# BG95_Power.net
KiCad netlist of a schematic drawn in Altium Designer
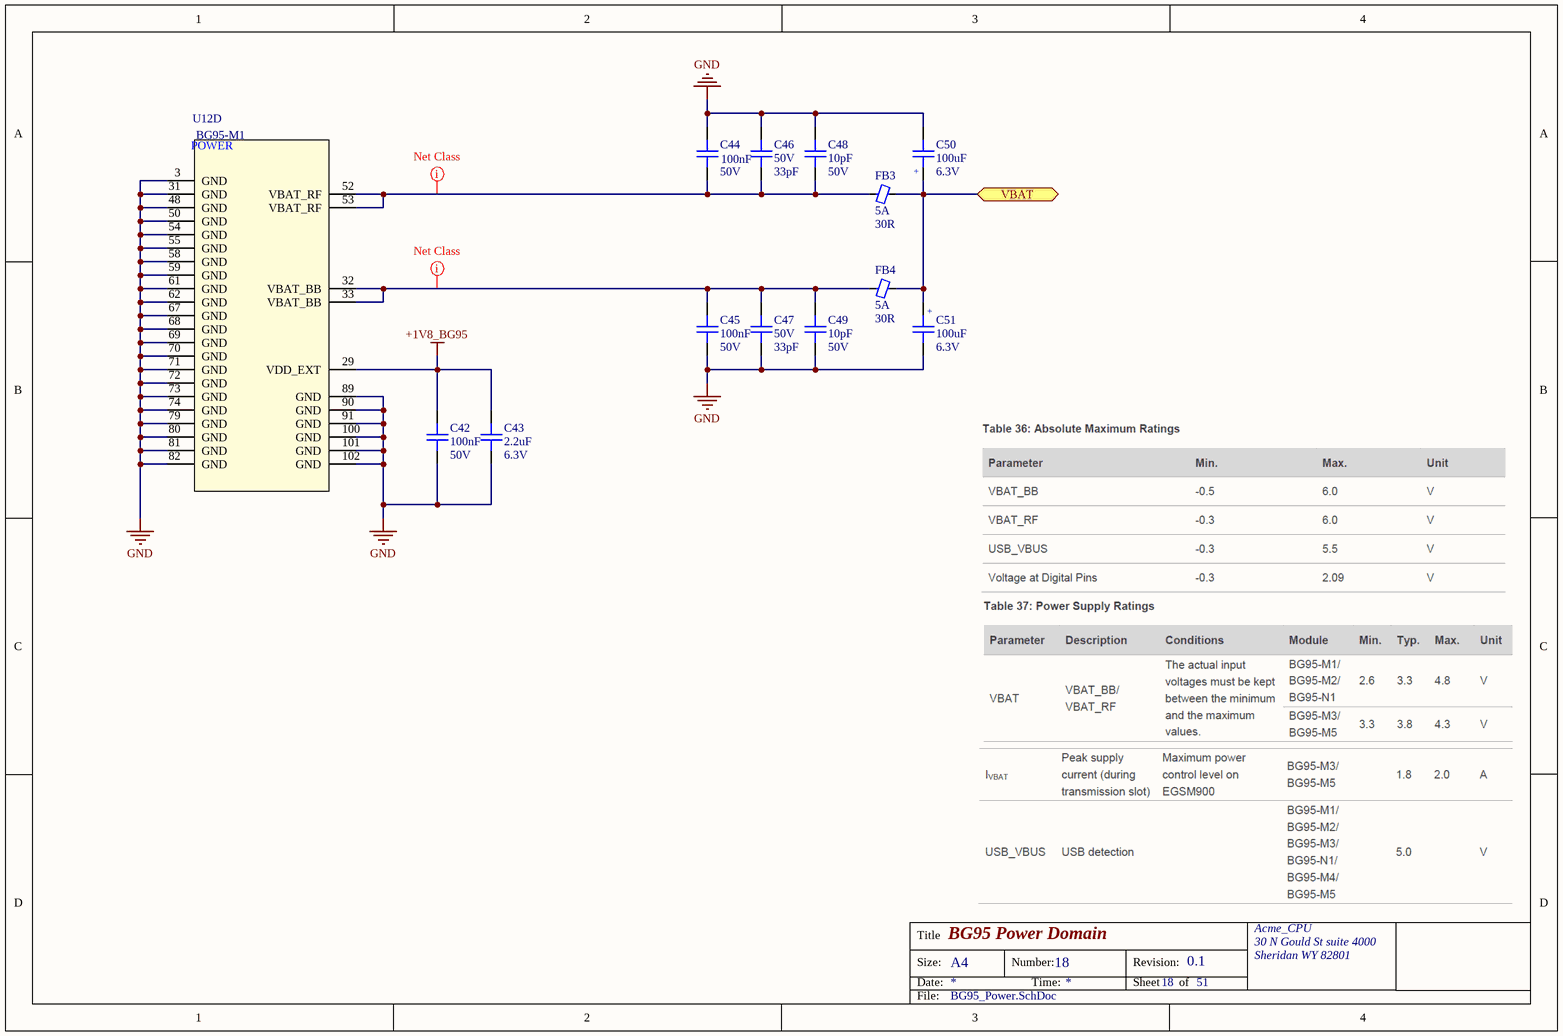
[diagram p0: BG95_Power.SchDoc]

(export (version "E")
  (design (tool "Eeschema 10.0.6"))
  (components
    (comp (ref "C42")
      (value "CAP CER 0.1UF 50V X7R 0402")
      (footprint "C0402")
      (description "0.1µF ±10% 50V Ceramic Capacitor X7R 0402 (1005 Metric)")
      (fields
        (field (name "MANUFACTURER") "TDK")
        (field (name "MANUFACTURER PART NUMBER") "CGA2B3X7R1H104K050BB")
        (field (name "CAPACITANCE") "100nF")
        (field (name "VOLTAGE") "50V")
      )
      (libsource (lib "capacitors_smd") (part "CAP CER 0.1UF 50V X7R 0402"))
    )
    (comp (ref "C43")
      (value "CAP CER 2.2UF 6.3V X5R 0402")
      (footprint "C0402")
      (description "2.2µF ±20% 6.3V Ceramic Capacitor X5R 0402 (1005 Metric)")
      (fields
        (field (name "MANUFACTURER") "Murata")
        (field (name "MANUFACTURER PART NUMBER") "GRM155R60J225ME15D")
        (field (name "CAPACITANCE") "2.2uF")
        (field (name "VOLTAGE") "6.3V")
      )
      (libsource (lib "capacitors_smd") (part "CAP CER 2.2UF 6.3V X5R 0402"))
    )
    (comp (ref "C44")
      (value "CAP CER 0.1UF 50V X7R 0402")
      (footprint "C0402")
      (description "0.1µF ±10% 50V Ceramic Capacitor X7R 0402 (1005 Metric)")
      (fields
        (field (name "MANUFACTURER") "TDK")
        (field (name "MANUFACTURER PART NUMBER") "CGA2B3X7R1H104K050BB")
        (field (name "CAPACITANCE") "100nF")
        (field (name "VOLTAGE") "50V")
      )
      (libsource (lib "capacitors_smd") (part "CAP CER 0.1UF 50V X7R 0402"))
    )
    (comp (ref "C45")
      (value "CAP CER 0.1UF 50V X7R 0402")
      (footprint "C0402")
      (description "0.1µF ±10% 50V Ceramic Capacitor X7R 0402 (1005 Metric)")
      (fields
        (field (name "MANUFACTURER") "TDK")
        (field (name "MANUFACTURER PART NUMBER") "CGA2B3X7R1H104K050BB")
        (field (name "CAPACITANCE") "100nF")
        (field (name "VOLTAGE") "50V")
      )
      (libsource (lib "capacitors_smd") (part "CAP CER 0.1UF 50V X7R 0402"))
    )
    (comp (ref "C46")
      (value "CAP CER 33PF 50V C0G/NPO 0402")
      (footprint "C0402")
      (description "33pF ±5% 50V Ceramic Capacitor C0G, NP0 0402 (1005 Metric)")
      (fields
        (field (name "MANUFACTURER") "Yageo")
        (field (name "MANUFACTURER PART NUMBER") "CC0402JRNPO9BN330")
        (field (name "VOLTAGE RATING") "50V")
        (field (name "CAPACITANCE") "33pF")
      )
      (libsource (lib "capacitors_smd") (part "CAP CER 33PF 50V C0G/NPO 0402"))
    )
    (comp (ref "C47")
      (value "CAP CER 33PF 50V C0G/NPO 0402")
      (footprint "C0402")
      (description "33pF ±5% 50V Ceramic Capacitor C0G, NP0 0402 (1005 Metric)")
      (fields
        (field (name "MANUFACTURER") "Yageo")
        (field (name "MANUFACTURER PART NUMBER") "CC0402JRNPO9BN330")
        (field (name "VOLTAGE RATING") "50V")
        (field (name "CAPACITANCE") "33pF")
      )
      (libsource (lib "capacitors_smd") (part "CAP CER 33PF 50V C0G/NPO 0402"))
    )
    (comp (ref "C48")
      (value "CAP CER 10PF 50V C0G/NP0 0402")
      (footprint "C0402")
      (description "10pF ±10% 50V Ceramic Capacitor C0G, NP0 0402 (1005 Metric)")
      (fields
        (field (name "MANUFACTURER") "KEMET")
        (field (name "MANUFACTURER PART NUMBER") "C0402C100K5GACTU")
        (field (name "CAPACITANCE") "10pF")
        (field (name "VOLTAGE RATING") "50V")
      )
      (libsource (lib "capacitors_smd") (part "CAP CER 10PF 50V C0G/NP0 0402"))
    )
    (comp (ref "C49")
      (value "CAP CER 10PF 50V C0G/NP0 0402")
      (footprint "C0402")
      (description "10pF ±10% 50V Ceramic Capacitor C0G, NP0 0402 (1005 Metric)")
      (fields
        (field (name "MANUFACTURER") "KEMET")
        (field (name "MANUFACTURER PART NUMBER") "C0402C100K5GACTU")
        (field (name "CAPACITANCE") "10pF")
        (field (name "VOLTAGE RATING") "50V")
      )
      (libsource (lib "capacitors_smd") (part "CAP CER 10PF 50V C0G/NP0 0402"))
    )
    (comp (ref "C50")
      (value "CAP ALUM 100 UF 20% 6.3 V SMD")
      (footprint "WCAP-ASLI_5x5.5")
      (description "100µF 6.3V Aluminum Electrolytic Capacitors Radial, Can - SMD  2000 Hrs @ 105°C")
      (fields
        (field (name "MANUFACTURER") "Wurth Elektronik")
        (field (name "MANUFACTURER PART NUMBER") "865080142007")
        (field (name "CAPACITANCE") "100uF")
        (field (name "VOLTAGE RATING") "6.3V")
      )
      (libsource (lib "capacitors_alum_electr_poly") (part "CAP ALUM 100 UF 20% 6.3 V SMD"))
    )
    (comp (ref "C51")
      (value "CAP ALUM 100 UF 20% 6.3 V SMD")
      (footprint "WCAP-ASLI_5x5.5")
      (description "100µF 6.3V Aluminum Electrolytic Capacitors Radial, Can - SMD  2000 Hrs @ 105°C")
      (fields
        (field (name "MANUFACTURER") "Wurth Elektronik")
        (field (name "MANUFACTURER PART NUMBER") "865080142007")
        (field (name "CAPACITANCE") "100uF")
        (field (name "VOLTAGE RATING") "6.3V")
      )
      (libsource (lib "capacitors_alum_electr_poly") (part "CAP ALUM 100 UF 20% 6.3 V SMD"))
    )
    (comp (ref "FB3")
      (value "MPZ1608S300ATAH0")
      (footprint "L0603")
      (description "30 Ohms @ 100MHz 1 Power Line Ferrite Bead 0603 (1608 Metric) 5A 10mOhm")
      (fields
        (field (name "MANUFACTURER") "TDK")
        (field (name "TOLERANCE") "25%")
        (field (name "CURRENT RATING") "5A")
        (field (name "IMPEDANCE") "30R")
      )
      (libsource (lib "ferrite_beads") (part "FERRITE BEAD 30 OHM 0603 1LN"))
    )
    (comp (ref "FB4")
      (value "MPZ1608S300ATAH0")
      (footprint "L0603")
      (description "30 Ohms @ 100MHz 1 Power Line Ferrite Bead 0603 (1608 Metric) 5A 10mOhm")
      (fields
        (field (name "MANUFACTURER") "TDK")
        (field (name "TOLERANCE") "25%")
        (field (name "CURRENT RATING") "5A")
        (field (name "IMPEDANCE") "30R")
      )
      (libsource (lib "ferrite_beads") (part "FERRITE BEAD 30 OHM 0603 1LN"))
    )
    (comp (ref "U12")
      (value "BG95-M1")
      (footprint "BG95")
      (description "LTE Cat M1, LTE Cat NB2 and EGPRS Transceiver Module Antenna Not Included Surface Mount")
      (fields (field (name "MANUFACTURER") "QUECTEL"))
      (libsource (lib "BLDC_Motor_Driver") (part "MOD BG95 RX TXRX CELLULAR LTE/NAV SMD"))
    )
  )
  (nets
    (net (code "1") (name "+1V8_BG95") (class "Default")
      (node (ref "C42") (pin "2") (pinfunction "2_2") (pintype "passive"))
      (node (ref "C43") (pin "2") (pinfunction "2_2") (pintype "passive"))
      (node (ref "U12") (pin "29") (pinfunction "VDD_EXT_29") (pintype "power_in"))
    )
    (net (code "2") (name "/VBAT") (class "Default")
      (node (ref "C50") (pin "1") (pinfunction "1_1") (pintype "passive"))
      (node (ref "C51") (pin "1") (pinfunction "1_1") (pintype "passive"))
      (node (ref "FB3") (pin "2") (pinfunction "2_2") (pintype "passive"))
      (node (ref "FB4") (pin "2") (pinfunction "2_2") (pintype "passive"))
    )
    (net (code "3") (name "GND") (class "Default")
      (node (ref "C42") (pin "1") (pinfunction "1_1") (pintype "passive"))
      (node (ref "C43") (pin "1") (pinfunction "1_1") (pintype "passive"))
      (node (ref "C44") (pin "2") (pinfunction "2_2") (pintype "passive"))
      (node (ref "C45") (pin "1") (pinfunction "1_1") (pintype "passive"))
      (node (ref "C46") (pin "2") (pinfunction "2_2") (pintype "passive"))
      (node (ref "C47") (pin "1") (pinfunction "1_1") (pintype "passive"))
      (node (ref "C48") (pin "2") (pinfunction "2_2") (pintype "passive"))
      (node (ref "C49") (pin "1") (pinfunction "1_1") (pintype "passive"))
      (node (ref "C50") (pin "2") (pinfunction "2_2") (pintype "passive"))
      (node (ref "C51") (pin "2") (pinfunction "2_2") (pintype "passive"))
      (node (ref "U12") (pin "100") (pinfunction "GND_100") (pintype "power_in"))
      (node (ref "U12") (pin "101") (pinfunction "GND_101") (pintype "power_in"))
      (node (ref "U12") (pin "102") (pinfunction "GND_102") (pintype "power_in"))
      (node (ref "U12") (pin "3") (pinfunction "GND_3") (pintype "power_in"))
      (node (ref "U12") (pin "31") (pinfunction "GND_31") (pintype "power_in"))
      (node (ref "U12") (pin "48") (pinfunction "GND_48") (pintype "power_in"))
      (node (ref "U12") (pin "50") (pinfunction "GND_50") (pintype "power_in"))
      (node (ref "U12") (pin "54") (pinfunction "GND_54") (pintype "power_in"))
      (node (ref "U12") (pin "55") (pinfunction "GND_55") (pintype "power_in"))
      (node (ref "U12") (pin "58") (pinfunction "GND_58") (pintype "power_in"))
      (node (ref "U12") (pin "59") (pinfunction "GND_59") (pintype "power_in"))
      (node (ref "U12") (pin "61") (pinfunction "GND_61") (pintype "power_in"))
      (node (ref "U12") (pin "62") (pinfunction "GND_62") (pintype "power_in"))
      (node (ref "U12") (pin "67") (pinfunction "GND_67") (pintype "power_in"))
      (node (ref "U12") (pin "68") (pinfunction "GND_68") (pintype "power_in"))
      (node (ref "U12") (pin "69") (pinfunction "GND_69") (pintype "power_in"))
      (node (ref "U12") (pin "70") (pinfunction "GND_70") (pintype "power_in"))
      (node (ref "U12") (pin "71") (pinfunction "GND_71") (pintype "power_in"))
      (node (ref "U12") (pin "72") (pinfunction "GND_72") (pintype "power_in"))
      (node (ref "U12") (pin "73") (pinfunction "GND_73") (pintype "power_in"))
      (node (ref "U12") (pin "74") (pinfunction "GND_74") (pintype "power_in"))
      (node (ref "U12") (pin "79") (pinfunction "GND_79") (pintype "power_in"))
      (node (ref "U12") (pin "80") (pinfunction "GND_80") (pintype "power_in"))
      (node (ref "U12") (pin "81") (pinfunction "GND_81") (pintype "power_in"))
      (node (ref "U12") (pin "82") (pinfunction "GND_82") (pintype "power_in"))
      (node (ref "U12") (pin "89") (pinfunction "GND_89") (pintype "power_in"))
      (node (ref "U12") (pin "90") (pinfunction "GND_90") (pintype "power_in"))
      (node (ref "U12") (pin "91") (pinfunction "GND_91") (pintype "power_in"))
    )
    (net (code "4") (name "Net-(C44-Pad1)") (class "Default")
      (node (ref "C44") (pin "1") (pinfunction "1_1") (pintype "passive"))
      (node (ref "C46") (pin "1") (pinfunction "1_1") (pintype "passive"))
      (node (ref "C48") (pin "1") (pinfunction "1_1") (pintype "passive"))
      (node (ref "FB3") (pin "1") (pinfunction "1_1") (pintype "passive"))
      (node (ref "U12") (pin "52") (pinfunction "VBAT_RF_52") (pintype "power_in"))
      (node (ref "U12") (pin "53") (pinfunction "VBAT_RF_53") (pintype "power_in"))
    )
    (net (code "5") (name "Net-(C45-Pad2)") (class "Default")
      (node (ref "C45") (pin "2") (pinfunction "2_2") (pintype "passive"))
      (node (ref "C47") (pin "2") (pinfunction "2_2") (pintype "passive"))
      (node (ref "C49") (pin "2") (pinfunction "2_2") (pintype "passive"))
      (node (ref "FB4") (pin "1") (pinfunction "1_1") (pintype "passive"))
      (node (ref "U12") (pin "32") (pinfunction "VBAT_BB_32") (pintype "power_in"))
      (node (ref "U12") (pin "33") (pinfunction "VBAT_BB_33") (pintype "power_in"))
    )
  )
)
